# ZX_Gesture_Sensor_SMD_v03.net
KiCad netlist of a schematic drawn in EAGLE
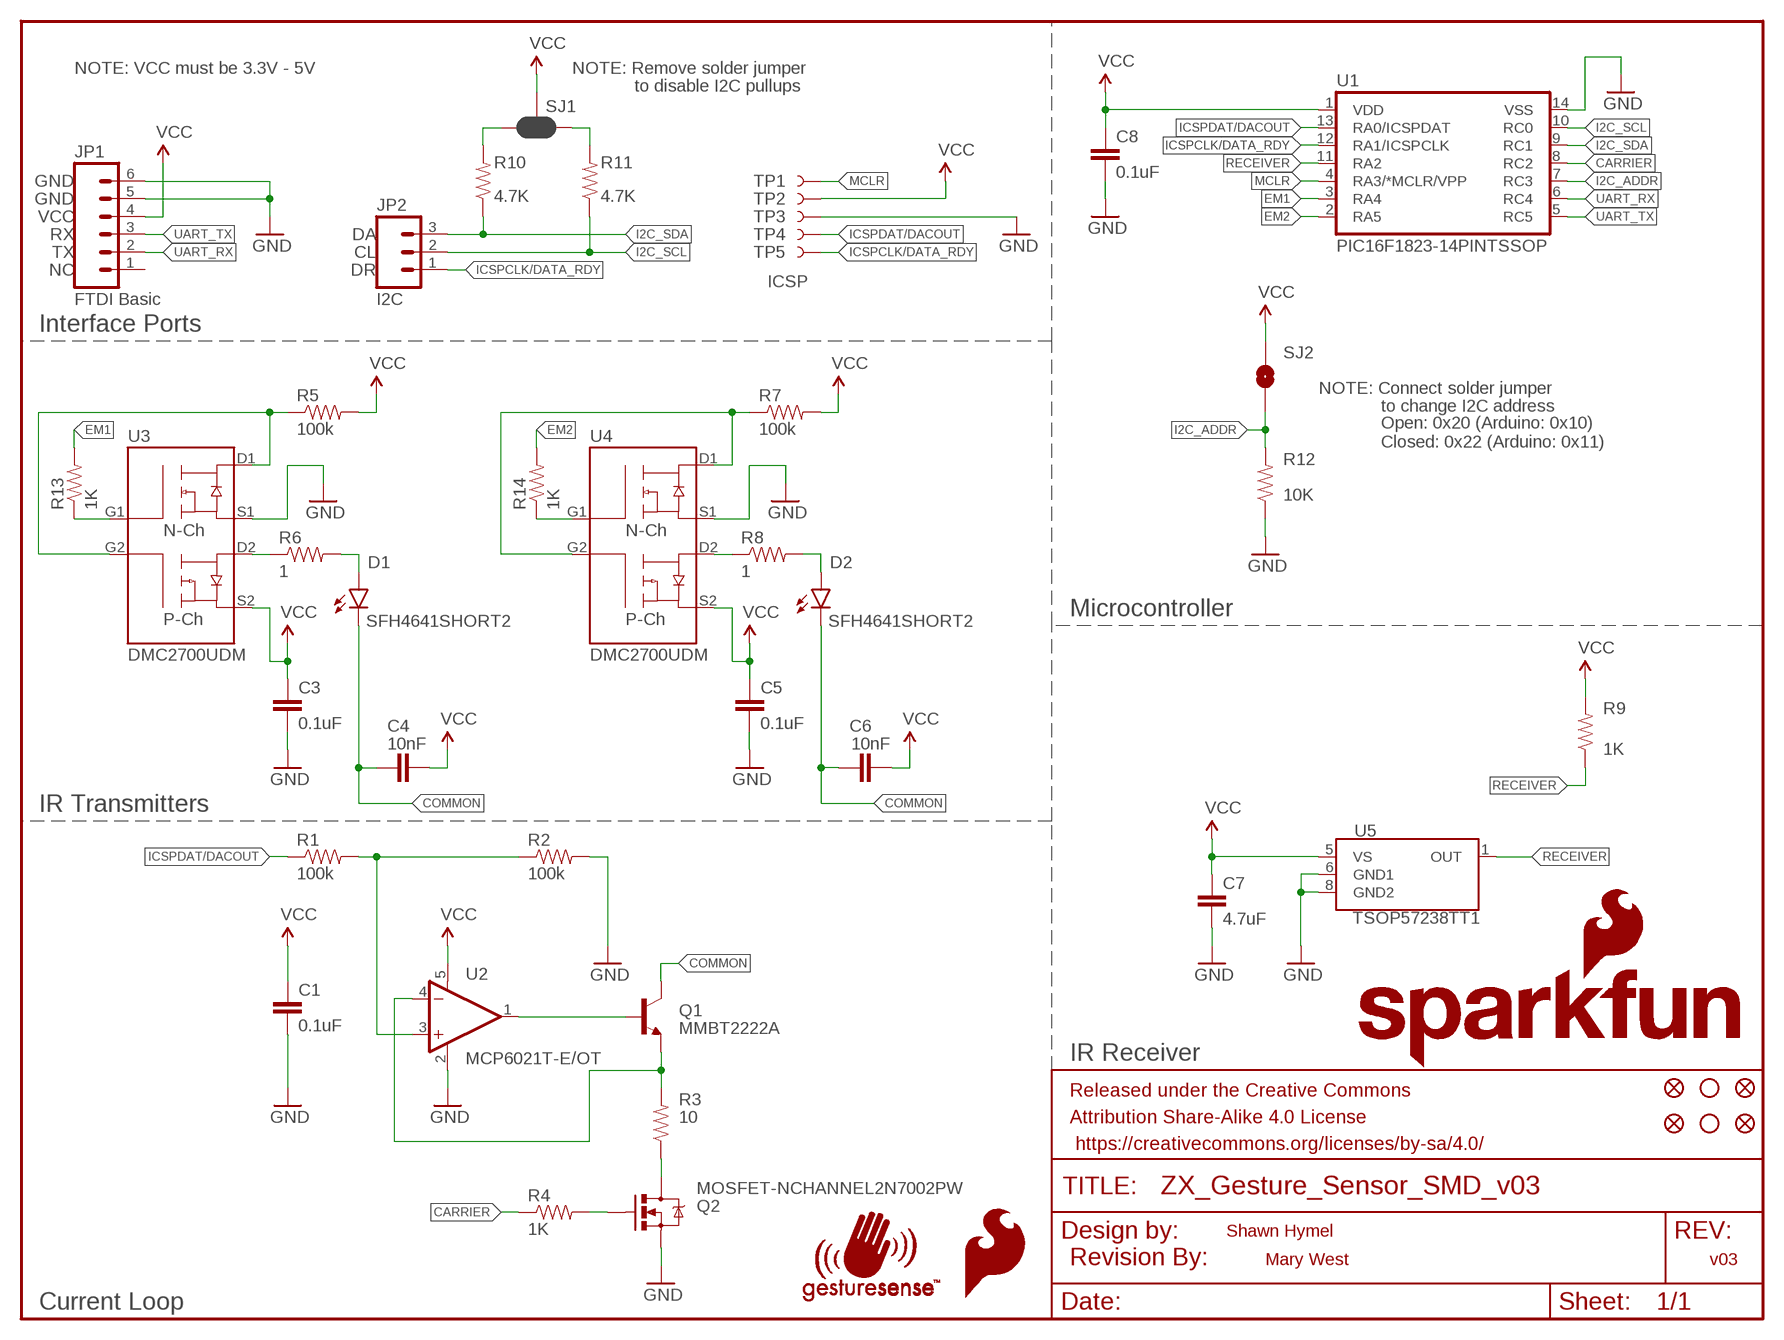
[diagram p0: schematic, sheet 1]

(export (version "E")
  (design (tool "Eeschema 10.0.6"))
  (components
    (comp (ref "C1")
      (value "0.1uF")
      (footprint "eagle-import:0603-CAP")
      (libsource (lib "eagle-import") (part "0.1UF-25V(+80/-20%)(0603)"))
    )
    (comp (ref "C3")
      (value "0.1uF")
      (footprint "eagle-import:0603-CAP")
      (libsource (lib "eagle-import") (part "0.1UF-25V(+80/-20%)(0603)"))
    )
    (comp (ref "C4")
      (value "10nF")
      (footprint "eagle-import:0603-CAP")
      (libsource (lib "eagle-import") (part "10NF/10000PF-50V-10%(0603)"))
    )
    (comp (ref "C5")
      (value "0.1uF")
      (footprint "eagle-import:0603-CAP")
      (libsource (lib "eagle-import") (part "0.1UF-25V(+80/-20%)(0603)"))
    )
    (comp (ref "C6")
      (value "10nF")
      (footprint "eagle-import:0603-CAP")
      (libsource (lib "eagle-import") (part "10NF/10000PF-50V-10%(0603)"))
    )
    (comp (ref "C7")
      (value "4.7uF")
      (footprint "eagle-import:0603-CAP")
      (libsource (lib "eagle-import") (part "4.7UF-6.3V-10%(0603)0603"))
    )
    (comp (ref "C8")
      (value "0.1uF")
      (footprint "eagle-import:0603-CAP")
      (libsource (lib "eagle-import") (part "0.1UF-25V(+80/-20%)(0603)"))
    )
    (comp (ref "D1")
      (value "SFH4641SHORT2")
      (footprint "eagle-import:SFH4641-SHORT2")
      (libsource (lib "eagle-import") (part "SFH4641SHORT2"))
    )
    (comp (ref "D2")
      (value "SFH4641SHORT2")
      (footprint "eagle-import:SFH4641-SHORT2")
      (libsource (lib "eagle-import") (part "SFH4641SHORT2"))
    )
    (comp (ref "FID1")
      (value "FIDUCIALUFIDUCIAL")
      (footprint "eagle-import:MICRO-FIDUCIAL")
      (libsource (lib "eagle-import") (part "FIDUCIALUFIDUCIAL"))
    )
    (comp (ref "FID2")
      (value "FIDUCIALUFIDUCIAL")
      (footprint "eagle-import:MICRO-FIDUCIAL")
      (libsource (lib "eagle-import") (part "FIDUCIALUFIDUCIAL"))
    )
    (comp (ref "FID3")
      (value "FIDUCIALUFIDUCIAL")
      (footprint "eagle-import:MICRO-FIDUCIAL")
      (libsource (lib "eagle-import") (part "FIDUCIALUFIDUCIAL"))
    )
    (comp (ref "FID4")
      (value "FIDUCIALUFIDUCIAL")
      (footprint "eagle-import:MICRO-FIDUCIAL")
      (libsource (lib "eagle-import") (part "FIDUCIALUFIDUCIAL"))
    )
    (comp (ref "FRAME1")
      (value "FRAME-LETTER")
      (footprint "eagle-import:CREATIVE_COMMONS")
      (libsource (lib "eagle-import") (part "FRAME-LETTER"))
    )
    (comp (ref "JP1")
      (value "M06NO_SILK_FEMALE_PTH")
      (footprint "eagle-import:1X06_NO_SILK")
      (libsource (lib "eagle-import") (part "M06NO_SILK_FEMALE_PTH"))
    )
    (comp (ref "JP2")
      (value "M031X03_NO_SILK")
      (footprint "eagle-import:1X03_NO_SILK")
      (libsource (lib "eagle-import") (part "M031X03_NO_SILK"))
    )
    (comp (ref "LOGO1")
      (value "REVISION")
      (footprint "eagle-import:REVISION")
      (libsource (lib "eagle-import") (part "REVISION"))
    )
    (comp (ref "LOGO2")
      (value "SFE_LOGO_FLAME.1_INCH")
      (footprint "eagle-import:SFE_LOGO_FLAME_.1")
      (libsource (lib "eagle-import") (part "SFE_LOGO_FLAME.1_INCH"))
    )
    (comp (ref "Q1")
      (value "MMBT2222A")
      (footprint "eagle-import:SOT23-3")
      (libsource (lib "eagle-import") (part "TRANSISTOR_NPNMMBT2222A"))
    )
    (comp (ref "Q2")
      (value "MOSFET-NCHANNEL2N7002PW")
      (footprint "eagle-import:SOT323")
      (libsource (lib "eagle-import") (part "MOSFET-NCHANNEL2N7002PW"))
    )
    (comp (ref "R1")
      (value "100k")
      (footprint "eagle-import:0603-RES")
      (libsource (lib "eagle-import") (part "100KOHM-1/10W-1%(0603)"))
    )
    (comp (ref "R2")
      (value "100k")
      (footprint "eagle-import:0603-RES")
      (libsource (lib "eagle-import") (part "100KOHM-1/10W-1%(0603)"))
    )
    (comp (ref "R3")
      (value "10")
      (footprint "eagle-import:0603-RES")
      (libsource (lib "eagle-import") (part "10OHM-1/10W-5%0603SMD"))
    )
    (comp (ref "R4")
      (value "1K")
      (footprint "eagle-import:0603-RES")
      (libsource (lib "eagle-import") (part "1KOHM-1/10W-1%(0603)"))
    )
    (comp (ref "R5")
      (value "100k")
      (footprint "eagle-import:0603-RES")
      (libsource (lib "eagle-import") (part "100KOHM-1/10W-1%(0603)"))
    )
    (comp (ref "R6")
      (value "1")
      (footprint "eagle-import:0603-RES")
      (libsource (lib "eagle-import") (part "1OHM1/10W1%(0603)"))
    )
    (comp (ref "R7")
      (value "100k")
      (footprint "eagle-import:0603-RES")
      (libsource (lib "eagle-import") (part "100KOHM-1/10W-1%(0603)"))
    )
    (comp (ref "R8")
      (value "1")
      (footprint "eagle-import:0603-RES")
      (libsource (lib "eagle-import") (part "1OHM1/10W1%(0603)"))
    )
    (comp (ref "R9")
      (value "1K")
      (footprint "eagle-import:0603-RES")
      (libsource (lib "eagle-import") (part "1KOHM-1/10W-1%(0603)"))
    )
    (comp (ref "R10")
      (value "4.7K")
      (footprint "eagle-import:0603-RES")
      (libsource (lib "eagle-import") (part "4.7KOHM-1/10W-1%(0603)"))
    )
    (comp (ref "R11")
      (value "4.7K")
      (footprint "eagle-import:0603-RES")
      (libsource (lib "eagle-import") (part "4.7KOHM-1/10W-1%(0603)"))
    )
    (comp (ref "R12")
      (value "10K")
      (footprint "eagle-import:0603-RES")
      (libsource (lib "eagle-import") (part "10KOHM-1/10W-1%(0603)0603"))
    )
    (comp (ref "R13")
      (value "1K")
      (footprint "eagle-import:0603-RES")
      (libsource (lib "eagle-import") (part "1KOHM-1/10W-1%(0603)"))
    )
    (comp (ref "R14")
      (value "1K")
      (footprint "eagle-import:0603-RES")
      (libsource (lib "eagle-import") (part "1KOHM-1/10W-1%(0603)"))
    )
    (comp (ref "SJ1")
      (value "JUMPER-PAD-3-NC_BY_PASTE")
      (footprint "eagle-import:PAD-JUMPER-3-NC_BY_PASTE_YES_SILK_FULL_BOX")
      (libsource (lib "eagle-import") (part "JUMPER-PAD-3-NC_BY_PASTE"))
    )
    (comp (ref "SJ2")
      (value "JUMPER-PAD-2-NOYES_SILK")
      (footprint "eagle-import:PAD-JUMPER-2-NO_YES_SILK")
      (libsource (lib "eagle-import") (part "JUMPER-PAD-2-NOYES_SILK"))
    )
    (comp (ref "STANDOFF1")
      (value "STAND-OFF")
      (footprint "eagle-import:STAND-OFF")
      (libsource (lib "eagle-import") (part "STAND-OFF"))
    )
    (comp (ref "STANDOFF2")
      (value "STAND-OFF")
      (footprint "eagle-import:STAND-OFF")
      (libsource (lib "eagle-import") (part "STAND-OFF"))
    )
    (comp (ref "TP1")
      (value "TEST-POINT3X4")
      (footprint "eagle-import:PAD.03X.04")
      (libsource (lib "eagle-import") (part "TEST-POINT3X4"))
    )
    (comp (ref "TP2")
      (value "TEST-POINT3X4")
      (footprint "eagle-import:PAD.03X.04")
      (libsource (lib "eagle-import") (part "TEST-POINT3X4"))
    )
    (comp (ref "TP3")
      (value "TEST-POINT3X4")
      (footprint "eagle-import:PAD.03X.04")
      (libsource (lib "eagle-import") (part "TEST-POINT3X4"))
    )
    (comp (ref "TP4")
      (value "TEST-POINT3X4")
      (footprint "eagle-import:PAD.03X.04")
      (libsource (lib "eagle-import") (part "TEST-POINT3X4"))
    )
    (comp (ref "TP5")
      (value "TEST-POINT3X4")
      (footprint "eagle-import:PAD.03X.04")
      (libsource (lib "eagle-import") (part "TEST-POINT3X4"))
    )
    (comp (ref "U$5")
      (value "SFE_LOGO_NAME_FLAME.1_INCH")
      (footprint "eagle-import:SFE_LOGO_NAME_FLAME_.1")
      (libsource (lib "eagle-import") (part "SFE_LOGO_NAME_FLAME.1_INCH"))
    )
    (comp (ref "U$6")
      (value "GESTURESENSE_LOGOSTEXT")
      (footprint "eagle-import:GESTURESENSE_TEXT")
      (libsource (lib "eagle-import") (part "GESTURESENSE_LOGOSTEXT"))
    )
    (comp (ref "U1")
      (value "PIC16F1823-14PINTSSOP")
      (footprint "eagle-import:TSSOP14")
      (libsource (lib "eagle-import") (part "PIC16F1823-14PINTSSOP"))
    )
    (comp (ref "U2")
      (value "MCP6021T-E/OT")
      (footprint "eagle-import:SOT23-5")
      (libsource (lib "eagle-import") (part "MCP6021T-E/OT"))
    )
    (comp (ref "U3")
      (value "DMC2700UDM")
      (footprint "eagle-import:SOT26")
      (libsource (lib "eagle-import") (part "DMC2700UDM"))
    )
    (comp (ref "U4")
      (value "DMC2700UDM")
      (footprint "eagle-import:SOT26")
      (libsource (lib "eagle-import") (part "DMC2700UDM"))
    )
    (comp (ref "U5")
      (value "TSOP57238TT1")
      (footprint "eagle-import:TSOP572")
      (libsource (lib "eagle-import") (part "TSOP57238TT1"))
    )
  )
  (nets
    (net (code "1") (name "CARRIER") (class "Default")
      (node (ref "R4") (pin "1") (pinfunction "1_1") (pintype "passive"))
      (node (ref "U1") (pin "8") (pinfunction "RC2_8") (pintype "bidirectional"))
    )
    (net (code "2") (name "COMMON") (class "Default")
      (node (ref "C4") (pin "1") (pinfunction "1_1") (pintype "passive"))
      (node (ref "C6") (pin "1") (pinfunction "1_1") (pintype "passive"))
      (node (ref "D1") (pin "C") (pinfunction "C_C") (pintype "passive"))
      (node (ref "D2") (pin "C") (pinfunction "C_C") (pintype "passive"))
      (node (ref "Q1") (pin "3") (pinfunction "C_3") (pintype "passive"))
    )
    (net (code "3") (name "EM1") (class "Default")
      (node (ref "R13") (pin "2") (pinfunction "2_2") (pintype "passive"))
      (node (ref "U1") (pin "3") (pinfunction "RA4_3") (pintype "bidirectional"))
    )
    (net (code "4") (name "EM2") (class "Default")
      (node (ref "R14") (pin "2") (pinfunction "2_2") (pintype "passive"))
      (node (ref "U1") (pin "2") (pinfunction "RA5_2") (pintype "bidirectional"))
    )
    (net (code "5") (name "GND") (class "Default")
      (node (ref "C1") (pin "2") (pinfunction "2_2") (pintype "passive"))
      (node (ref "C3") (pin "2") (pinfunction "2_2") (pintype "passive"))
      (node (ref "C5") (pin "2") (pinfunction "2_2") (pintype "passive"))
      (node (ref "C7") (pin "2") (pinfunction "2_2") (pintype "passive"))
      (node (ref "C8") (pin "2") (pinfunction "2_2") (pintype "passive"))
      (node (ref "JP1") (pin "5") (pinfunction "5_5") (pintype "passive"))
      (node (ref "JP1") (pin "6") (pinfunction "6_6") (pintype "passive"))
      (node (ref "Q2") (pin "2") (pinfunction "S_2") (pintype "passive"))
      (node (ref "R12") (pin "1") (pinfunction "1_1") (pintype "passive"))
      (node (ref "R2") (pin "2") (pinfunction "2_2") (pintype "passive"))
      (node (ref "TP3") (pin "P$1") (pinfunction "1_P$1") (pintype "bidirectional"))
      (node (ref "U1") (pin "14") (pinfunction "VSS_14") (pintype "power_in"))
      (node (ref "U2") (pin "2") (pinfunction "V-_2") (pintype "power_in"))
      (node (ref "U3") (pin "S1") (pinfunction "S1_S1") (pintype "bidirectional"))
      (node (ref "U4") (pin "S1") (pinfunction "S1_S1") (pintype "bidirectional"))
      (node (ref "U5") (pin "6") (pinfunction "GND1_6") (pintype "bidirectional"))
      (node (ref "U5") (pin "8") (pinfunction "GND2_8") (pintype "bidirectional"))
    )
    (net (code "6") (name "I2C_ADDR") (class "Default")
      (node (ref "R12") (pin "2") (pinfunction "2_2") (pintype "passive"))
      (node (ref "SJ2") (pin "1") (pinfunction "1_1") (pintype "passive"))
      (node (ref "U1") (pin "7") (pinfunction "RC3_7") (pintype "bidirectional"))
    )
    (net (code "7") (name "I2C_SCL") (class "Default")
      (node (ref "JP2") (pin "2") (pinfunction "2_2") (pintype "passive"))
      (node (ref "R11") (pin "1") (pinfunction "1_1") (pintype "passive"))
      (node (ref "U1") (pin "10") (pinfunction "RC0_10") (pintype "bidirectional"))
    )
    (net (code "8") (name "I2C_SDA") (class "Default")
      (node (ref "JP2") (pin "3") (pinfunction "3_3") (pintype "passive"))
      (node (ref "R10") (pin "1") (pinfunction "1_1") (pintype "passive"))
      (node (ref "U1") (pin "9") (pinfunction "RC1_9") (pintype "bidirectional"))
    )
    (net (code "9") (name "ICSPCLK{slash}DATA_RDY") (class "Default")
      (node (ref "JP2") (pin "1") (pinfunction "1_1") (pintype "passive"))
      (node (ref "TP5") (pin "P$1") (pinfunction "1_P$1") (pintype "bidirectional"))
      (node (ref "U1") (pin "12") (pinfunction "RA1/ICSPCLK_12") (pintype "bidirectional"))
    )
    (net (code "10") (name "ICSPDAT{slash}DACOUT") (class "Default")
      (node (ref "R1") (pin "1") (pinfunction "1_1") (pintype "passive"))
      (node (ref "TP4") (pin "P$1") (pinfunction "1_P$1") (pintype "bidirectional"))
      (node (ref "U1") (pin "13") (pinfunction "RA0/ICSPDAT_13") (pintype "bidirectional"))
    )
    (net (code "11") (name "MCLR") (class "Default")
      (node (ref "TP1") (pin "P$1") (pinfunction "1_P$1") (pintype "bidirectional"))
      (node (ref "U1") (pin "4") (pinfunction "RA3/*MCLR/VPP_4") (pintype "input"))
    )
    (net (code "12") (name "Net-(D1-PadA)") (class "Default")
      (node (ref "D1") (pin "A") (pinfunction "A_A") (pintype "passive"))
      (node (ref "R6") (pin "2") (pinfunction "2_2") (pintype "passive"))
    )
    (net (code "13") (name "Net-(D2-PadA)") (class "Default")
      (node (ref "D2") (pin "A") (pinfunction "A_A") (pintype "passive"))
      (node (ref "R8") (pin "2") (pinfunction "2_2") (pintype "passive"))
    )
    (net (code "14") (name "Net-(Q1-B)") (class "Default")
      (node (ref "Q1") (pin "1") (pinfunction "B_1") (pintype "passive"))
      (node (ref "U2") (pin "1") (pinfunction "OUT_1") (pintype "output"))
    )
    (net (code "15") (name "Net-(Q1-E)") (class "Default")
      (node (ref "Q1") (pin "2") (pinfunction "E_2") (pintype "passive"))
      (node (ref "R3") (pin "2") (pinfunction "2_2") (pintype "passive"))
      (node (ref "U2") (pin "4") (pinfunction "-IN_4") (pintype "input"))
    )
    (net (code "16") (name "Net-(Q2-D)") (class "Default")
      (node (ref "Q2") (pin "3") (pinfunction "D_3") (pintype "passive"))
      (node (ref "R3") (pin "1") (pinfunction "1_1") (pintype "passive"))
    )
    (net (code "17") (name "Net-(Q2-G)") (class "Default")
      (node (ref "Q2") (pin "1") (pinfunction "G_1") (pintype "passive"))
      (node (ref "R4") (pin "2") (pinfunction "2_2") (pintype "passive"))
    )
    (net (code "18") (name "Net-(R5-Pad1)") (class "Default")
      (node (ref "R5") (pin "1") (pinfunction "1_1") (pintype "passive"))
      (node (ref "U3") (pin "D1") (pinfunction "D1_D1") (pintype "bidirectional"))
      (node (ref "U3") (pin "G2") (pinfunction "G2_G2") (pintype "bidirectional"))
    )
    (net (code "19") (name "Net-(R6-Pad1)") (class "Default")
      (node (ref "R6") (pin "1") (pinfunction "1_1") (pintype "passive"))
      (node (ref "U3") (pin "D2") (pinfunction "D2_D2") (pintype "bidirectional"))
    )
    (net (code "20") (name "Net-(R7-Pad1)") (class "Default")
      (node (ref "R7") (pin "1") (pinfunction "1_1") (pintype "passive"))
      (node (ref "U4") (pin "D1") (pinfunction "D1_D1") (pintype "bidirectional"))
      (node (ref "U4") (pin "G2") (pinfunction "G2_G2") (pintype "bidirectional"))
    )
    (net (code "21") (name "Net-(R8-Pad1)") (class "Default")
      (node (ref "R8") (pin "1") (pinfunction "1_1") (pintype "passive"))
      (node (ref "U4") (pin "D2") (pinfunction "D2_D2") (pintype "bidirectional"))
    )
    (net (code "22") (name "Net-(R10-Pad2)") (class "Default")
      (node (ref "R10") (pin "2") (pinfunction "2_2") (pintype "passive"))
      (node (ref "SJ1") (pin "3") (pinfunction "3_3") (pintype "passive"))
    )
    (net (code "23") (name "Net-(R11-Pad2)") (class "Default")
      (node (ref "R11") (pin "2") (pinfunction "2_2") (pintype "passive"))
      (node (ref "SJ1") (pin "1") (pinfunction "1_1") (pintype "passive"))
    )
    (net (code "24") (name "Net-(R13-Pad1)") (class "Default")
      (node (ref "R13") (pin "1") (pinfunction "1_1") (pintype "passive"))
      (node (ref "U3") (pin "G1") (pinfunction "G1_G1") (pintype "bidirectional"))
    )
    (net (code "25") (name "Net-(R14-Pad1)") (class "Default")
      (node (ref "R14") (pin "1") (pinfunction "1_1") (pintype "passive"))
      (node (ref "U4") (pin "G1") (pinfunction "G1_G1") (pintype "bidirectional"))
    )
    (net (code "26") (name "Net-(U2-+IN)") (class "Default")
      (node (ref "R1") (pin "2") (pinfunction "2_2") (pintype "passive"))
      (node (ref "R2") (pin "1") (pinfunction "1_1") (pintype "passive"))
      (node (ref "U2") (pin "3") (pinfunction "+IN_3") (pintype "input"))
    )
    (net (code "27") (name "RECEIVER") (class "Default")
      (node (ref "R9") (pin "1") (pinfunction "1_1") (pintype "passive"))
      (node (ref "U1") (pin "11") (pinfunction "RA2_11") (pintype "bidirectional"))
      (node (ref "U5") (pin "1") (pinfunction "OUT_1") (pintype "bidirectional"))
    )
    (net (code "28") (name "UART_RX") (class "Default")
      (node (ref "JP1") (pin "2") (pinfunction "2_2") (pintype "passive"))
      (node (ref "U1") (pin "6") (pinfunction "RC4_6") (pintype "bidirectional"))
    )
    (net (code "29") (name "UART_TX") (class "Default")
      (node (ref "JP1") (pin "3") (pinfunction "3_3") (pintype "passive"))
      (node (ref "U1") (pin "5") (pinfunction "RC5_5") (pintype "bidirectional"))
    )
    (net (code "30") (name "VCC") (class "Default")
      (node (ref "C1") (pin "1") (pinfunction "1_1") (pintype "passive"))
      (node (ref "C3") (pin "1") (pinfunction "1_1") (pintype "passive"))
      (node (ref "C4") (pin "2") (pinfunction "2_2") (pintype "passive"))
      (node (ref "C5") (pin "1") (pinfunction "1_1") (pintype "passive"))
      (node (ref "C6") (pin "2") (pinfunction "2_2") (pintype "passive"))
      (node (ref "C7") (pin "1") (pinfunction "1_1") (pintype "passive"))
      (node (ref "C8") (pin "1") (pinfunction "1_1") (pintype "passive"))
      (node (ref "JP1") (pin "4") (pinfunction "4_4") (pintype "passive"))
      (node (ref "R5") (pin "2") (pinfunction "2_2") (pintype "passive"))
      (node (ref "R7") (pin "2") (pinfunction "2_2") (pintype "passive"))
      (node (ref "R9") (pin "2") (pinfunction "2_2") (pintype "passive"))
      (node (ref "SJ1") (pin "2") (pinfunction "2_2") (pintype "passive"))
      (node (ref "SJ2") (pin "2") (pinfunction "2_2") (pintype "passive"))
      (node (ref "TP2") (pin "P$1") (pinfunction "1_P$1") (pintype "bidirectional"))
      (node (ref "U1") (pin "1") (pinfunction "VDD_1") (pintype "power_in"))
      (node (ref "U2") (pin "5") (pinfunction "V+_5") (pintype "power_in"))
      (node (ref "U3") (pin "S2") (pinfunction "S2_S2") (pintype "bidirectional"))
      (node (ref "U4") (pin "S2") (pinfunction "S2_S2") (pintype "bidirectional"))
      (node (ref "U5") (pin "5") (pinfunction "VS_5") (pintype "bidirectional"))
    )
    (net (code "31") (name "unconnected-(JP1-Pad1)") (class "Default")
      (node (ref "JP1") (pin "1") (pinfunction "1_1") (pintype "passive"))
    )
  )
)
